# Serial_Card_V2.net
KiCad netlist of a schematic drawn in EAGLE
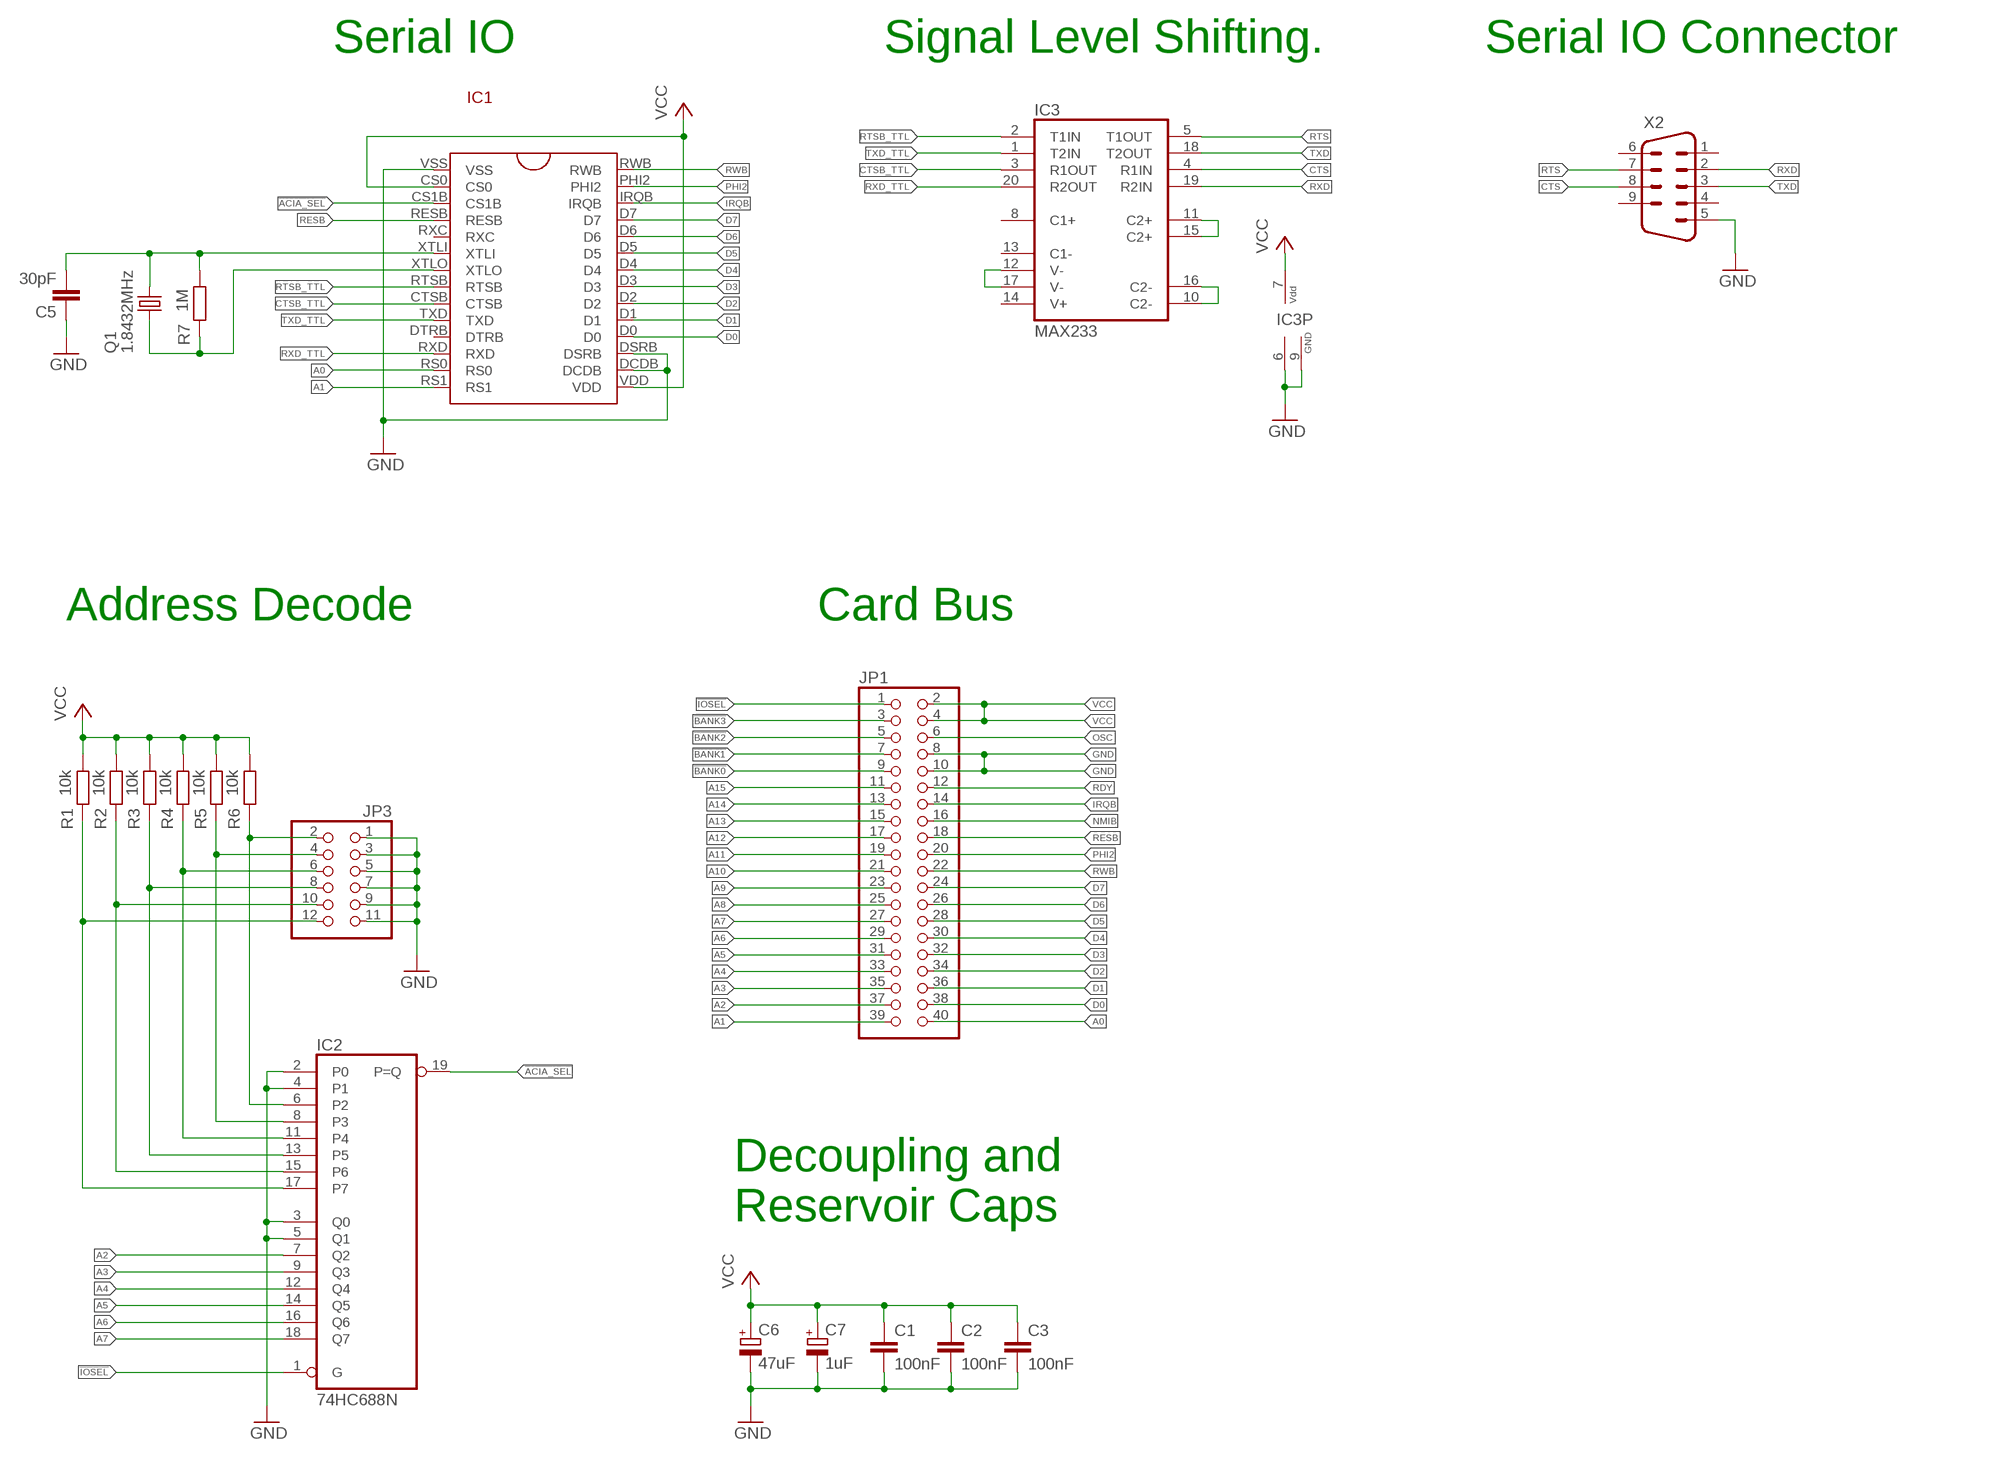
[diagram p0: schematic, sheet 1]

(export (version "E")
  (design (tool "Eeschema 10.0.6"))
  (components
    (comp (ref "C1")
      (value "100nF")
      (footprint "eagle-import:C050-025X075")
      (libsource (lib "eagle-import") (part "C-EU050-025X075"))
    )
    (comp (ref "C2")
      (value "100nF")
      (footprint "eagle-import:C050-025X075")
      (libsource (lib "eagle-import") (part "C-EU050-025X075"))
    )
    (comp (ref "C3")
      (value "100nF")
      (footprint "eagle-import:C050-025X075")
      (libsource (lib "eagle-import") (part "C-EU050-025X075"))
    )
    (comp (ref "C5")
      (value "30pF")
      (footprint "eagle-import:C050-025X075")
      (libsource (lib "eagle-import") (part "C-EU050-025X075"))
    )
    (comp (ref "C6")
      (value "47uF")
      (footprint "eagle-import:E2,5-7")
      (libsource (lib "eagle-import") (part "CPOL-EUE2.5-7"))
    )
    (comp (ref "C7")
      (value "1uF")
      (footprint "eagle-import:E2,5-5")
      (libsource (lib "eagle-import") (part "CPOL-EUE2.5-5"))
    )
    (comp (ref "IC1")
      (value "W65C51N-DIP")
      (footprint "eagle-import:W65C51N-DIP")
      (libsource (lib "eagle-import") (part "W65C51N-DIP"))
    )
    (comp (ref "IC2")
      (value "74HC688N")
      (footprint "eagle-import:DIL20")
      (libsource (lib "eagle-import") (part "74688NHC"))
    )
    (comp (ref "IC3")
      (value "MAX233")
      (footprint "eagle-import:DIL20")
      (libsource (lib "eagle-import") (part "MAX233"))
    )
    (comp (ref "JP1")
      (value "PINHD-2X20/90")
      (footprint "eagle-import:2X20_90")
      (libsource (lib "eagle-import") (part "PINHD-2X20/90"))
    )
    (comp (ref "JP3")
      (value "PINHD-2X6")
      (footprint "eagle-import:2X06")
      (libsource (lib "eagle-import") (part "PINHD-2X6"))
    )
    (comp (ref "Q1")
      (value "1.8432MHz")
      (footprint "eagle-import:HC49_S")
      (libsource (lib "eagle-import") (part "CRYSTALHC49S"))
    )
    (comp (ref "R1")
      (value "10k")
      (footprint "eagle-import:0207_2V")
      (libsource (lib "eagle-import") (part "R-EU_0207/2V"))
    )
    (comp (ref "R2")
      (value "10k")
      (footprint "eagle-import:0207_2V")
      (libsource (lib "eagle-import") (part "R-EU_0207/2V"))
    )
    (comp (ref "R3")
      (value "10k")
      (footprint "eagle-import:0207_2V")
      (libsource (lib "eagle-import") (part "R-EU_0207/2V"))
    )
    (comp (ref "R4")
      (value "10k")
      (footprint "eagle-import:0207_2V")
      (libsource (lib "eagle-import") (part "R-EU_0207/2V"))
    )
    (comp (ref "R5")
      (value "10k")
      (footprint "eagle-import:0207_2V")
      (libsource (lib "eagle-import") (part "R-EU_0207/2V"))
    )
    (comp (ref "R6")
      (value "10k")
      (footprint "eagle-import:0207_2V")
      (libsource (lib "eagle-import") (part "R-EU_0207/2V"))
    )
    (comp (ref "R7")
      (value "1M")
      (footprint "eagle-import:0207_2V")
      (libsource (lib "eagle-import") (part "R-EU_0207/2V"))
    )
    (comp (ref "X2")
      (value "M09HP")
      (footprint "eagle-import:M09HP")
      (libsource (lib "eagle-import") (part "M09HP"))
    )
  )
  (nets
    (net (code "1") (name "/~{ACIA_SEL}") (class "Default")
      (node (ref "IC1") (pin "CS1B") (pinfunction "CS1B_CS1B") (pintype "input"))
      (node (ref "IC2") (pin "19") (pinfunction "P=Q_19") (pintype "output"))
    )
    (net (code "2") (name "/~{BANK0}") (class "Default")
      (node (ref "JP1") (pin "9") (pinfunction "9_9") (pintype "passive"))
    )
    (net (code "3") (name "/~{BANK1}") (class "Default")
      (node (ref "JP1") (pin "7") (pinfunction "7_7") (pintype "passive"))
    )
    (net (code "4") (name "/~{BANK2}") (class "Default")
      (node (ref "JP1") (pin "5") (pinfunction "5_5") (pintype "passive"))
    )
    (net (code "5") (name "/~{BANK3}") (class "Default")
      (node (ref "JP1") (pin "3") (pinfunction "3_3") (pintype "passive"))
    )
    (net (code "6") (name "/~{IOSEL}") (class "Default")
      (node (ref "IC2") (pin "1") (pinfunction "G_1") (pintype "input"))
      (node (ref "JP1") (pin "1") (pinfunction "1_1") (pintype "passive"))
    )
    (net (code "7") (name "A0") (class "Default")
      (node (ref "IC1") (pin "RS0") (pinfunction "RS0_RS0") (pintype "input"))
      (node (ref "JP1") (pin "40") (pinfunction "40_40") (pintype "passive"))
    )
    (net (code "8") (name "A1") (class "Default")
      (node (ref "IC1") (pin "RS1") (pinfunction "RS1_RS1") (pintype "input"))
      (node (ref "JP1") (pin "39") (pinfunction "39_39") (pintype "passive"))
    )
    (net (code "9") (name "A2") (class "Default")
      (node (ref "IC2") (pin "7") (pinfunction "Q2_7") (pintype "input"))
      (node (ref "JP1") (pin "37") (pinfunction "37_37") (pintype "passive"))
    )
    (net (code "10") (name "A3") (class "Default")
      (node (ref "IC2") (pin "9") (pinfunction "Q3_9") (pintype "input"))
      (node (ref "JP1") (pin "35") (pinfunction "35_35") (pintype "passive"))
    )
    (net (code "11") (name "A4") (class "Default")
      (node (ref "IC2") (pin "12") (pinfunction "Q4_12") (pintype "input"))
      (node (ref "JP1") (pin "33") (pinfunction "33_33") (pintype "passive"))
    )
    (net (code "12") (name "A5") (class "Default")
      (node (ref "IC2") (pin "14") (pinfunction "Q5_14") (pintype "input"))
      (node (ref "JP1") (pin "31") (pinfunction "31_31") (pintype "passive"))
    )
    (net (code "13") (name "A6") (class "Default")
      (node (ref "IC2") (pin "16") (pinfunction "Q6_16") (pintype "input"))
      (node (ref "JP1") (pin "29") (pinfunction "29_29") (pintype "passive"))
    )
    (net (code "14") (name "A7") (class "Default")
      (node (ref "IC2") (pin "18") (pinfunction "Q7_18") (pintype "input"))
      (node (ref "JP1") (pin "27") (pinfunction "27_27") (pintype "passive"))
    )
    (net (code "15") (name "A8") (class "Default")
      (node (ref "JP1") (pin "25") (pinfunction "25_25") (pintype "passive"))
    )
    (net (code "16") (name "A9") (class "Default")
      (node (ref "JP1") (pin "23") (pinfunction "23_23") (pintype "passive"))
    )
    (net (code "17") (name "A10") (class "Default")
      (node (ref "JP1") (pin "21") (pinfunction "21_21") (pintype "passive"))
    )
    (net (code "18") (name "A11") (class "Default")
      (node (ref "JP1") (pin "19") (pinfunction "19_19") (pintype "passive"))
    )
    (net (code "19") (name "A12") (class "Default")
      (node (ref "JP1") (pin "17") (pinfunction "17_17") (pintype "passive"))
    )
    (net (code "20") (name "A13") (class "Default")
      (node (ref "JP1") (pin "15") (pinfunction "15_15") (pintype "passive"))
    )
    (net (code "21") (name "A14") (class "Default")
      (node (ref "JP1") (pin "13") (pinfunction "13_13") (pintype "passive"))
    )
    (net (code "22") (name "A15") (class "Default")
      (node (ref "JP1") (pin "11") (pinfunction "11_11") (pintype "passive"))
    )
    (net (code "23") (name "CTS") (class "Default")
      (node (ref "IC3") (pin "4") (pinfunction "R1IN_4") (pintype "input"))
      (node (ref "X2") (pin "8") (pinfunction "8_8") (pintype "passive"))
    )
    (net (code "24") (name "CTSB_TTL") (class "Default")
      (node (ref "IC1") (pin "CTSB") (pinfunction "CTSB_CTSB") (pintype "input"))
      (node (ref "IC3") (pin "3") (pinfunction "R1OUT_3") (pintype "output"))
    )
    (net (code "25") (name "D0") (class "Default")
      (node (ref "IC1") (pin "D0") (pinfunction "D0_D0") (pintype "bidirectional"))
      (node (ref "JP1") (pin "38") (pinfunction "38_38") (pintype "passive"))
    )
    (net (code "26") (name "D1") (class "Default")
      (node (ref "IC1") (pin "D1") (pinfunction "D1_D1") (pintype "bidirectional"))
      (node (ref "JP1") (pin "36") (pinfunction "36_36") (pintype "passive"))
    )
    (net (code "27") (name "D2") (class "Default")
      (node (ref "IC1") (pin "D2") (pinfunction "D2_D2") (pintype "bidirectional"))
      (node (ref "JP1") (pin "34") (pinfunction "34_34") (pintype "passive"))
    )
    (net (code "28") (name "D3") (class "Default")
      (node (ref "IC1") (pin "D3") (pinfunction "D3_D3") (pintype "bidirectional"))
      (node (ref "JP1") (pin "32") (pinfunction "32_32") (pintype "passive"))
    )
    (net (code "29") (name "D4") (class "Default")
      (node (ref "IC1") (pin "D4") (pinfunction "D4_D4") (pintype "bidirectional"))
      (node (ref "JP1") (pin "30") (pinfunction "30_30") (pintype "passive"))
    )
    (net (code "30") (name "D5") (class "Default")
      (node (ref "IC1") (pin "D5") (pinfunction "D5_D5") (pintype "bidirectional"))
      (node (ref "JP1") (pin "28") (pinfunction "28_28") (pintype "passive"))
    )
    (net (code "31") (name "D6") (class "Default")
      (node (ref "IC1") (pin "D6") (pinfunction "D6_D6") (pintype "bidirectional"))
      (node (ref "JP1") (pin "26") (pinfunction "26_26") (pintype "passive"))
    )
    (net (code "32") (name "D7") (class "Default")
      (node (ref "IC1") (pin "D7") (pinfunction "D7_D7") (pintype "bidirectional"))
      (node (ref "JP1") (pin "24") (pinfunction "24_24") (pintype "passive"))
    )
    (net (code "33") (name "GND") (class "Default")
      (node (ref "C1") (pin "2") (pinfunction "2_2") (pintype "passive"))
      (node (ref "C2") (pin "2") (pinfunction "2_2") (pintype "passive"))
      (node (ref "C3") (pin "2") (pinfunction "2_2") (pintype "passive"))
      (node (ref "C5") (pin "1") (pinfunction "1_1") (pintype "passive"))
      (node (ref "C6") (pin "-") (pinfunction "-_-") (pintype "passive"))
      (node (ref "C7") (pin "-") (pinfunction "-_-") (pintype "passive"))
      (node (ref "IC1") (pin "DCDB") (pinfunction "DCDB_DCDB") (pintype "input"))
      (node (ref "IC1") (pin "DSRB") (pinfunction "DSRB_DSRB") (pintype "input"))
      (node (ref "IC1") (pin "VSS") (pinfunction "VSS_VSS") (pintype "power_in"))
      (node (ref "IC2") (pin "2") (pinfunction "P0_2") (pintype "input"))
      (node (ref "IC2") (pin "3") (pinfunction "Q0_3") (pintype "input"))
      (node (ref "IC2") (pin "4") (pinfunction "P1_4") (pintype "input"))
      (node (ref "IC2") (pin "5") (pinfunction "Q1_5") (pintype "input"))
      (node (ref "IC3") (pin "6") (pinfunction "GND_6") (pintype "power_in"))
      (node (ref "IC3") (pin "9") (pinfunction "GND_9") (pintype "power_in"))
      (node (ref "JP1") (pin "10") (pinfunction "10_10") (pintype "passive"))
      (node (ref "JP1") (pin "8") (pinfunction "8_8") (pintype "passive"))
      (node (ref "JP3") (pin "1") (pinfunction "1_1") (pintype "passive"))
      (node (ref "JP3") (pin "11") (pinfunction "11_11") (pintype "passive"))
      (node (ref "JP3") (pin "3") (pinfunction "3_3") (pintype "passive"))
      (node (ref "JP3") (pin "5") (pinfunction "5_5") (pintype "passive"))
      (node (ref "JP3") (pin "7") (pinfunction "7_7") (pintype "passive"))
      (node (ref "JP3") (pin "9") (pinfunction "9_9") (pintype "passive"))
      (node (ref "X2") (pin "5") (pinfunction "5_5") (pintype "passive"))
    )
    (net (code "34") (name "IRQB") (class "Default")
      (node (ref "IC1") (pin "IRQB") (pinfunction "IRQB_IRQB") (pintype "output"))
      (node (ref "JP1") (pin "14") (pinfunction "14_14") (pintype "passive"))
    )
    (net (code "35") (name "NMIB") (class "Default")
      (node (ref "JP1") (pin "16") (pinfunction "16_16") (pintype "passive"))
    )
    (net (code "36") (name "Net-(C5-Pad2)") (class "Default")
      (node (ref "C5") (pin "2") (pinfunction "2_2") (pintype "passive"))
      (node (ref "IC1") (pin "XTLI") (pinfunction "XTLI_XTLI") (pintype "input"))
      (node (ref "Q1") (pin "2") (pinfunction "2_2") (pintype "passive"))
      (node (ref "R7") (pin "2") (pinfunction "2_2") (pintype "passive"))
    )
    (net (code "37") (name "Net-(IC1-PadXTLO)") (class "Default")
      (node (ref "IC1") (pin "XTLO") (pinfunction "XTLO_XTLO") (pintype "output"))
      (node (ref "Q1") (pin "1") (pinfunction "1_1") (pintype "passive"))
      (node (ref "R7") (pin "1") (pinfunction "1_1") (pintype "passive"))
    )
    (net (code "38") (name "Net-(IC2A-P2)") (class "Default")
      (node (ref "IC2") (pin "6") (pinfunction "P2_6") (pintype "input"))
      (node (ref "JP3") (pin "2") (pinfunction "2_2") (pintype "passive"))
      (node (ref "R6") (pin "1") (pinfunction "1_1") (pintype "passive"))
    )
    (net (code "39") (name "Net-(IC2A-P3)") (class "Default")
      (node (ref "IC2") (pin "8") (pinfunction "P3_8") (pintype "input"))
      (node (ref "JP3") (pin "4") (pinfunction "4_4") (pintype "passive"))
      (node (ref "R5") (pin "1") (pinfunction "1_1") (pintype "passive"))
    )
    (net (code "40") (name "Net-(IC2A-P4)") (class "Default")
      (node (ref "IC2") (pin "11") (pinfunction "P4_11") (pintype "input"))
      (node (ref "JP3") (pin "6") (pinfunction "6_6") (pintype "passive"))
      (node (ref "R4") (pin "1") (pinfunction "1_1") (pintype "passive"))
    )
    (net (code "41") (name "Net-(IC2A-P5)") (class "Default")
      (node (ref "IC2") (pin "13") (pinfunction "P5_13") (pintype "input"))
      (node (ref "JP3") (pin "8") (pinfunction "8_8") (pintype "passive"))
      (node (ref "R3") (pin "1") (pinfunction "1_1") (pintype "passive"))
    )
    (net (code "42") (name "Net-(IC2A-P6)") (class "Default")
      (node (ref "IC2") (pin "15") (pinfunction "P6_15") (pintype "input"))
      (node (ref "JP3") (pin "10") (pinfunction "10_10") (pintype "passive"))
      (node (ref "R2") (pin "1") (pinfunction "1_1") (pintype "passive"))
    )
    (net (code "43") (name "Net-(IC2A-P7)") (class "Default")
      (node (ref "IC2") (pin "17") (pinfunction "P7_17") (pintype "input"))
      (node (ref "JP3") (pin "12") (pinfunction "12_12") (pintype "passive"))
      (node (ref "R1") (pin "1") (pinfunction "1_1") (pintype "passive"))
    )
    (net (code "44") (name "Net-(IC3A-C2+-Pad11)") (class "Default")
      (node (ref "IC3") (pin "11") (pinfunction "C2+_11") (pintype "bidirectional"))
      (node (ref "IC3") (pin "15") (pinfunction "C2+_15") (pintype "bidirectional"))
    )
    (net (code "45") (name "Net-(IC3A-C2--Pad10)") (class "Default")
      (node (ref "IC3") (pin "10") (pinfunction "C2-_10") (pintype "bidirectional"))
      (node (ref "IC3") (pin "16") (pinfunction "C2-_16") (pintype "bidirectional"))
    )
    (net (code "46") (name "Net-(IC3A-V--Pad12)") (class "Default")
      (node (ref "IC3") (pin "12") (pinfunction "V-_12") (pintype "bidirectional"))
      (node (ref "IC3") (pin "17") (pinfunction "V-_17") (pintype "bidirectional"))
    )
    (net (code "47") (name "OSC") (class "Default")
      (node (ref "JP1") (pin "6") (pinfunction "6_6") (pintype "passive"))
    )
    (net (code "48") (name "PHI2") (class "Default")
      (node (ref "IC1") (pin "PHI2") (pinfunction "PHI2_PHI2") (pintype "input"))
      (node (ref "JP1") (pin "20") (pinfunction "20_20") (pintype "passive"))
    )
    (net (code "49") (name "RDY") (class "Default")
      (node (ref "JP1") (pin "12") (pinfunction "12_12") (pintype "passive"))
    )
    (net (code "50") (name "RESB") (class "Default")
      (node (ref "IC1") (pin "RESB") (pinfunction "RESB_RESB") (pintype "input"))
      (node (ref "JP1") (pin "18") (pinfunction "18_18") (pintype "passive"))
    )
    (net (code "51") (name "RTS") (class "Default")
      (node (ref "IC3") (pin "5") (pinfunction "T1OUT_5") (pintype "output"))
      (node (ref "X2") (pin "7") (pinfunction "7_7") (pintype "passive"))
    )
    (net (code "52") (name "RTSB_TTL") (class "Default")
      (node (ref "IC1") (pin "RTSB") (pinfunction "RTSB_RTSB") (pintype "output"))
      (node (ref "IC3") (pin "2") (pinfunction "T1IN_2") (pintype "input"))
    )
    (net (code "53") (name "RWB") (class "Default")
      (node (ref "IC1") (pin "RWB") (pinfunction "RWB_RWB") (pintype "input"))
      (node (ref "JP1") (pin "22") (pinfunction "22_22") (pintype "passive"))
    )
    (net (code "54") (name "RXD") (class "Default")
      (node (ref "IC3") (pin "19") (pinfunction "R2IN_19") (pintype "input"))
      (node (ref "X2") (pin "2") (pinfunction "2_2") (pintype "passive"))
    )
    (net (code "55") (name "RXD_TTL") (class "Default")
      (node (ref "IC1") (pin "RXD") (pinfunction "RXD_RXD") (pintype "input"))
      (node (ref "IC3") (pin "20") (pinfunction "R2OUT_20") (pintype "output"))
    )
    (net (code "56") (name "TXD") (class "Default")
      (node (ref "IC3") (pin "18") (pinfunction "T2OUT_18") (pintype "output"))
      (node (ref "X2") (pin "3") (pinfunction "3_3") (pintype "passive"))
    )
    (net (code "57") (name "TXD_TTL") (class "Default")
      (node (ref "IC1") (pin "TXD") (pinfunction "TXD_TXD") (pintype "output"))
      (node (ref "IC3") (pin "1") (pinfunction "T2IN_1") (pintype "input"))
    )
    (net (code "58") (name "VCC") (class "Default")
      (node (ref "C1") (pin "1") (pinfunction "1_1") (pintype "passive"))
      (node (ref "C2") (pin "1") (pinfunction "1_1") (pintype "passive"))
      (node (ref "C3") (pin "1") (pinfunction "1_1") (pintype "passive"))
      (node (ref "C6") (pin "+") (pinfunction "+_+") (pintype "passive"))
      (node (ref "C7") (pin "+") (pinfunction "+_+") (pintype "passive"))
      (node (ref "IC1") (pin "CS0") (pinfunction "CS0_CS0") (pintype "input"))
      (node (ref "IC1") (pin "VDD") (pinfunction "VDD_VDD") (pintype "power_in"))
      (node (ref "IC3") (pin "7") (pinfunction "VDD_7") (pintype "power_in"))
      (node (ref "JP1") (pin "2") (pinfunction "2_2") (pintype "passive"))
      (node (ref "JP1") (pin "4") (pinfunction "4_4") (pintype "passive"))
      (node (ref "R1") (pin "2") (pinfunction "2_2") (pintype "passive"))
      (node (ref "R2") (pin "2") (pinfunction "2_2") (pintype "passive"))
      (node (ref "R3") (pin "2") (pinfunction "2_2") (pintype "passive"))
      (node (ref "R4") (pin "2") (pinfunction "2_2") (pintype "passive"))
      (node (ref "R5") (pin "2") (pinfunction "2_2") (pintype "passive"))
      (node (ref "R6") (pin "2") (pinfunction "2_2") (pintype "passive"))
    )
    (net (code "59") (name "unconnected-(IC1-PadDTRB)") (class "Default")
      (node (ref "IC1") (pin "DTRB") (pinfunction "DTRB_DTRB") (pintype "output"))
    )
    (net (code "60") (name "unconnected-(IC1-PadRXC)") (class "Default")
      (node (ref "IC1") (pin "RXC") (pinfunction "RXC_RXC") (pintype "bidirectional"))
    )
    (net (code "61") (name "unconnected-(IC3A-C1+-Pad8)") (class "Default")
      (node (ref "IC3") (pin "8") (pinfunction "C1+_8") (pintype "bidirectional"))
    )
    (net (code "62") (name "unconnected-(IC3A-C1--Pad13)") (class "Default")
      (node (ref "IC3") (pin "13") (pinfunction "C1-_13") (pintype "bidirectional"))
    )
    (net (code "63") (name "unconnected-(IC3A-V+-Pad14)") (class "Default")
      (node (ref "IC3") (pin "14") (pinfunction "V+_14") (pintype "bidirectional"))
    )
    (net (code "64") (name "unconnected-(X2-Pad1)") (class "Default")
      (node (ref "X2") (pin "1") (pinfunction "1_1") (pintype "passive"))
    )
    (net (code "65") (name "unconnected-(X2-Pad4)") (class "Default")
      (node (ref "X2") (pin "4") (pinfunction "4_4") (pintype "passive"))
    )
    (net (code "66") (name "unconnected-(X2-Pad6)") (class "Default")
      (node (ref "X2") (pin "6") (pinfunction "6_6") (pintype "passive"))
    )
    (net (code "67") (name "unconnected-(X2-Pad9)") (class "Default")
      (node (ref "X2") (pin "9") (pinfunction "9_9") (pintype "passive"))
    )
  )
)
